# Built-in.net
KiCad netlist of a schematic drawn in EAGLE
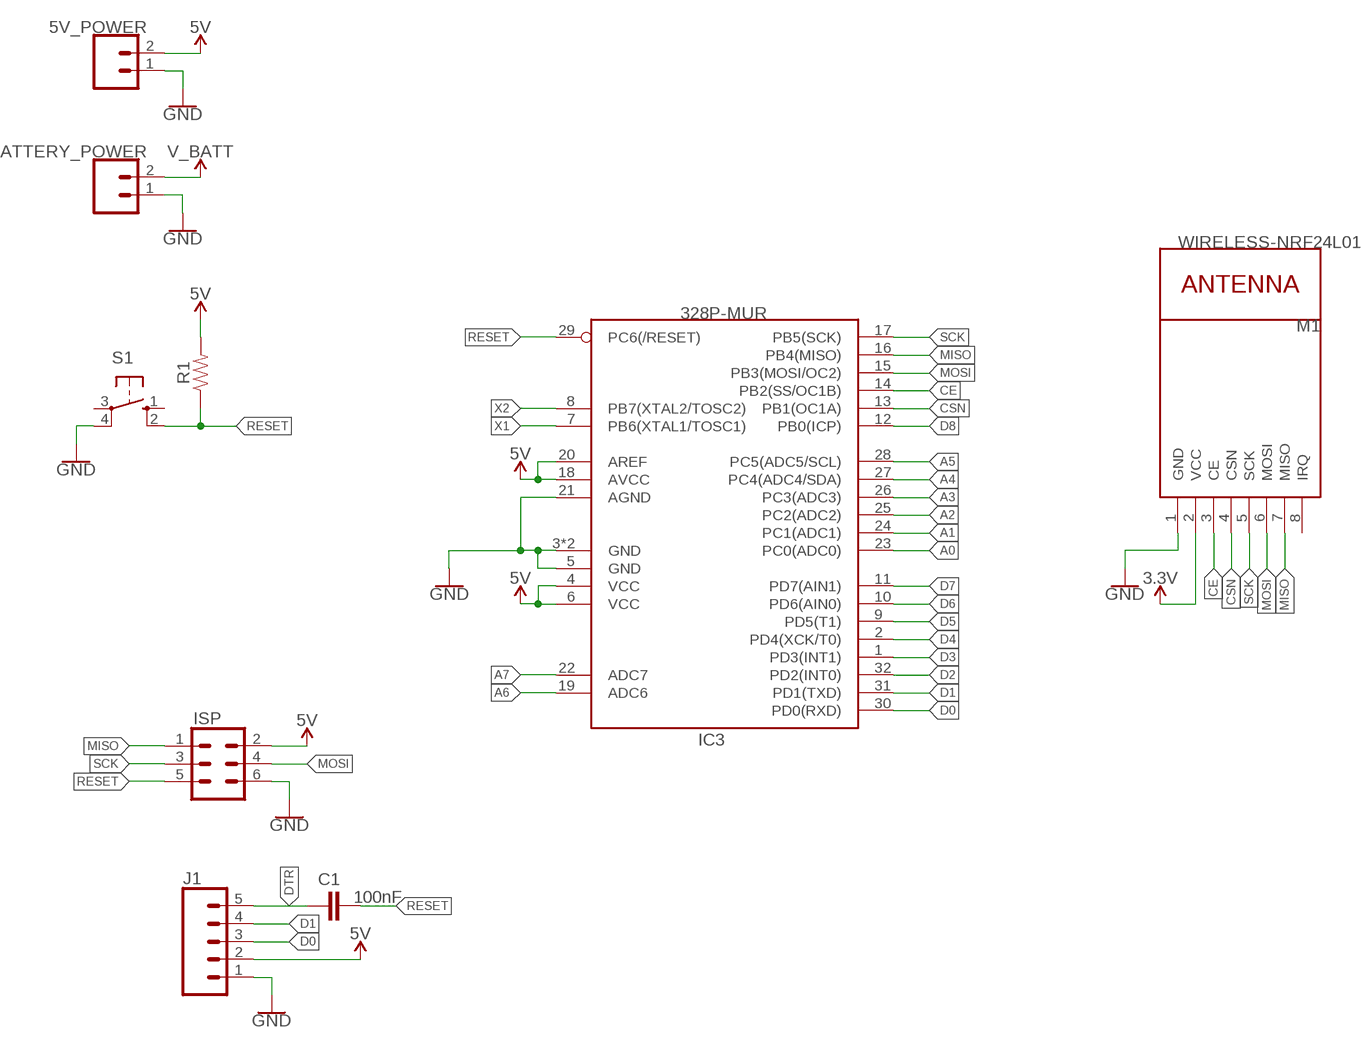
[diagram p0: schematic, sheet 1]

(export (version "E")
  (design (tool "Eeschema 10.0.6"))
  (components
    (comp (ref "5V_POWER")
      (value "CONN_025MM")
      (footprint "eagle-import:SCREWTERMINAL-5MM-2")
      (libsource (lib "eagle-import") (part "CONN_025MM"))
    )
    (comp (ref "BATTERY_POWER")
      (value "CONN_025MM")
      (footprint "eagle-import:SCREWTERMINAL-5MM-2")
      (libsource (lib "eagle-import") (part "CONN_025MM"))
    )
    (comp (ref "C1")
      (value "100nF")
      (footprint "eagle-import:0603")
      (libsource (lib "eagle-import") (part "10NF-0603-50V-10%"))
    )
    (comp (ref "IC3")
      (value "328P-MUR")
      (footprint "eagle-import:VQFN32")
      (fields (field (name "MANUFACTURER") "ATMEL"))
      (libsource (lib "eagle-import") (part "ATMEGA328P-32MUR"))
    )
    (comp (ref "ISP")
      (value "CONN_03X22X3_SILK_MALE_PTH")
      (footprint "eagle-import:2X3")
      (libsource (lib "eagle-import") (part "CONN_03X22X3_SILK_MALE_PTH"))
    )
    (comp (ref "J1")
      (value "CONN_05")
      (footprint "eagle-import:1X05")
      (libsource (lib "eagle-import") (part "CONN_05"))
    )
    (comp (ref "M1")
      (value "WIRELESS-NRF24L01")
      (footprint "eagle-import:WIRELESS-NRF24L01")
      (libsource (lib "eagle-import") (part "WIRELESS-NRF24L01"))
    )
    (comp (ref "R1")
      (value "RESISTOR0402")
      (footprint "eagle-import:0402")
      (libsource (lib "eagle-import") (part "RESISTOR0402"))
    )
    (comp (ref "S1")
      (value "40-XX")
      (footprint "eagle-import:B3F-40XX")
      (fields (field (name "MF") "OMRON COMPONENTS USA") (field (name "MPN") "B3F-4000"))
      (libsource (lib "eagle-import") (part "40-XX"))
    )
  )
  (nets
    (net (code "1") (name "3.3V") (class "Default")
      (node (ref "M1") (pin "2") (pinfunction "VCC_2") (pintype "power_in"))
    )
    (net (code "2") (name "5V") (class "Default")
      (node (ref "5V_POWER") (pin "2") (pinfunction "2_2") (pintype "passive"))
      (node (ref "IC3") (pin "18") (pinfunction "AVCC_18") (pintype "bidirectional"))
      (node (ref "IC3") (pin "20") (pinfunction "AREF_20") (pintype "bidirectional"))
      (node (ref "IC3") (pin "4") (pinfunction "VCC_4") (pintype "bidirectional"))
      (node (ref "IC3") (pin "6") (pinfunction "VCC_6") (pintype "bidirectional"))
      (node (ref "ISP") (pin "2") (pinfunction "2_2") (pintype "bidirectional"))
      (node (ref "J1") (pin "2") (pinfunction "2_2") (pintype "passive"))
      (node (ref "R1") (pin "2") (pinfunction "2_2") (pintype "passive"))
    )
    (net (code "3") (name "A0") (class "Default")
      (node (ref "IC3") (pin "23") (pinfunction "PC0(ADC0)_23") (pintype "bidirectional"))
    )
    (net (code "4") (name "A1") (class "Default")
      (node (ref "IC3") (pin "24") (pinfunction "PC1(ADC1)_24") (pintype "bidirectional"))
    )
    (net (code "5") (name "A2") (class "Default")
      (node (ref "IC3") (pin "25") (pinfunction "PC2(ADC2)_25") (pintype "bidirectional"))
    )
    (net (code "6") (name "A3") (class "Default")
      (node (ref "IC3") (pin "26") (pinfunction "PC3(ADC3)_26") (pintype "bidirectional"))
    )
    (net (code "7") (name "A4") (class "Default")
      (node (ref "IC3") (pin "27") (pinfunction "PC4(ADC4/SDA)_27") (pintype "bidirectional"))
    )
    (net (code "8") (name "A5") (class "Default")
      (node (ref "IC3") (pin "28") (pinfunction "PC5(ADC5/SCL)_28") (pintype "bidirectional"))
    )
    (net (code "9") (name "A6") (class "Default")
      (node (ref "IC3") (pin "19") (pinfunction "ADC6_19") (pintype "bidirectional"))
    )
    (net (code "10") (name "A7") (class "Default")
      (node (ref "IC3") (pin "22") (pinfunction "ADC7_22") (pintype "bidirectional"))
    )
    (net (code "11") (name "CE") (class "Default")
      (node (ref "IC3") (pin "14") (pinfunction "PB2(SS/OC1B)_14") (pintype "bidirectional"))
      (node (ref "M1") (pin "3") (pinfunction "CE_3") (pintype "bidirectional"))
    )
    (net (code "12") (name "CSN") (class "Default")
      (node (ref "IC3") (pin "13") (pinfunction "PB1(OC1A)_13") (pintype "bidirectional"))
      (node (ref "M1") (pin "4") (pinfunction "CSN_4") (pintype "bidirectional"))
    )
    (net (code "13") (name "D0") (class "Default")
      (node (ref "IC3") (pin "30") (pinfunction "PD0(RXD)_30") (pintype "bidirectional"))
      (node (ref "J1") (pin "3") (pinfunction "3_3") (pintype "passive"))
    )
    (net (code "14") (name "D1") (class "Default")
      (node (ref "IC3") (pin "31") (pinfunction "PD1(TXD)_31") (pintype "bidirectional"))
      (node (ref "J1") (pin "4") (pinfunction "4_4") (pintype "passive"))
    )
    (net (code "15") (name "D2") (class "Default")
      (node (ref "IC3") (pin "32") (pinfunction "PD2(INT0)_32") (pintype "bidirectional"))
    )
    (net (code "16") (name "D3") (class "Default")
      (node (ref "IC3") (pin "1") (pinfunction "PD3(INT1)_1") (pintype "bidirectional"))
    )
    (net (code "17") (name "D4") (class "Default")
      (node (ref "IC3") (pin "2") (pinfunction "PD4(XCK/T0)_2") (pintype "bidirectional"))
    )
    (net (code "18") (name "D5") (class "Default")
      (node (ref "IC3") (pin "9") (pinfunction "PD5(T1)_9") (pintype "bidirectional"))
    )
    (net (code "19") (name "D6") (class "Default")
      (node (ref "IC3") (pin "10") (pinfunction "PD6(AIN0)_10") (pintype "bidirectional"))
    )
    (net (code "20") (name "D7") (class "Default")
      (node (ref "IC3") (pin "11") (pinfunction "PD7(AIN1)_11") (pintype "bidirectional"))
    )
    (net (code "21") (name "D8") (class "Default")
      (node (ref "IC3") (pin "12") (pinfunction "PB0(ICP)_12") (pintype "bidirectional"))
    )
    (net (code "22") (name "DTR") (class "Default")
      (node (ref "C1") (pin "1") (pinfunction "1_1") (pintype "passive"))
      (node (ref "J1") (pin "5") (pinfunction "5_5") (pintype "passive"))
    )
    (net (code "23") (name "GND") (class "Default")
      (node (ref "5V_POWER") (pin "1") (pinfunction "1_1") (pintype "passive"))
      (node (ref "BATTERY_POWER") (pin "1") (pinfunction "1_1") (pintype "passive"))
      (node (ref "IC3") (pin "21") (pinfunction "AGND_21") (pintype "bidirectional"))
      (node (ref "IC3") (pin "3") (pinfunction "GND_3") (pintype "bidirectional"))
      (node (ref "IC3") (pin "33") (pinfunction "GND_33") (pintype "bidirectional"))
      (node (ref "IC3") (pin "5") (pinfunction "GND_5") (pintype "bidirectional"))
      (node (ref "ISP") (pin "6") (pinfunction "6_6") (pintype "bidirectional"))
      (node (ref "J1") (pin "1") (pinfunction "1_1") (pintype "passive"))
      (node (ref "M1") (pin "1") (pinfunction "GND_1") (pintype "power_in"))
      (node (ref "S1") (pin "4") (pinfunction "P1_4") (pintype "passive"))
    )
    (net (code "24") (name "MISO") (class "Default")
      (node (ref "IC3") (pin "16") (pinfunction "PB4(MISO)_16") (pintype "bidirectional"))
      (node (ref "ISP") (pin "1") (pinfunction "1_1") (pintype "bidirectional"))
      (node (ref "M1") (pin "7") (pinfunction "MISO_7") (pintype "bidirectional"))
    )
    (net (code "25") (name "MOSI") (class "Default")
      (node (ref "IC3") (pin "15") (pinfunction "PB3(MOSI/OC2)_15") (pintype "bidirectional"))
      (node (ref "ISP") (pin "4") (pinfunction "4_4") (pintype "bidirectional"))
      (node (ref "M1") (pin "6") (pinfunction "MOSI_6") (pintype "bidirectional"))
    )
    (net (code "26") (name "RESET") (class "Default")
      (node (ref "C1") (pin "2") (pinfunction "2_2") (pintype "passive"))
      (node (ref "IC3") (pin "29") (pinfunction "PC6(/RESET)_29") (pintype "bidirectional"))
      (node (ref "ISP") (pin "5") (pinfunction "5_5") (pintype "bidirectional"))
      (node (ref "R1") (pin "1") (pinfunction "1_1") (pintype "passive"))
      (node (ref "S1") (pin "2") (pinfunction "S1_2") (pintype "passive"))
    )
    (net (code "27") (name "SCK") (class "Default")
      (node (ref "IC3") (pin "17") (pinfunction "PB5(SCK)_17") (pintype "bidirectional"))
      (node (ref "ISP") (pin "3") (pinfunction "3_3") (pintype "bidirectional"))
      (node (ref "M1") (pin "5") (pinfunction "SCK_5") (pintype "bidirectional"))
    )
    (net (code "28") (name "V_BATT") (class "Default")
      (node (ref "BATTERY_POWER") (pin "2") (pinfunction "2_2") (pintype "passive"))
    )
    (net (code "29") (name "X1") (class "Default")
      (node (ref "IC3") (pin "7") (pinfunction "PB6(XTAL1/TOSC1)_7") (pintype "bidirectional"))
    )
    (net (code "30") (name "X2") (class "Default")
      (node (ref "IC3") (pin "8") (pinfunction "PB7(XTAL2/TOSC2)_8") (pintype "bidirectional"))
    )
    (net (code "31") (name "unconnected-(M1-IRQ-Pad8)") (class "Default")
      (node (ref "M1") (pin "8") (pinfunction "IRQ_8") (pintype "bidirectional"))
    )
    (net (code "32") (name "unconnected-(S1-P-Pad3)") (class "Default")
      (node (ref "S1") (pin "3") (pinfunction "P_3") (pintype "passive"))
    )
    (net (code "33") (name "unconnected-(S1-S-Pad1)") (class "Default")
      (node (ref "S1") (pin "1") (pinfunction "S_1") (pintype "passive"))
    )
  )
)
